# my_board.net
KiCad netlist of a schematic drawn in EAGLE
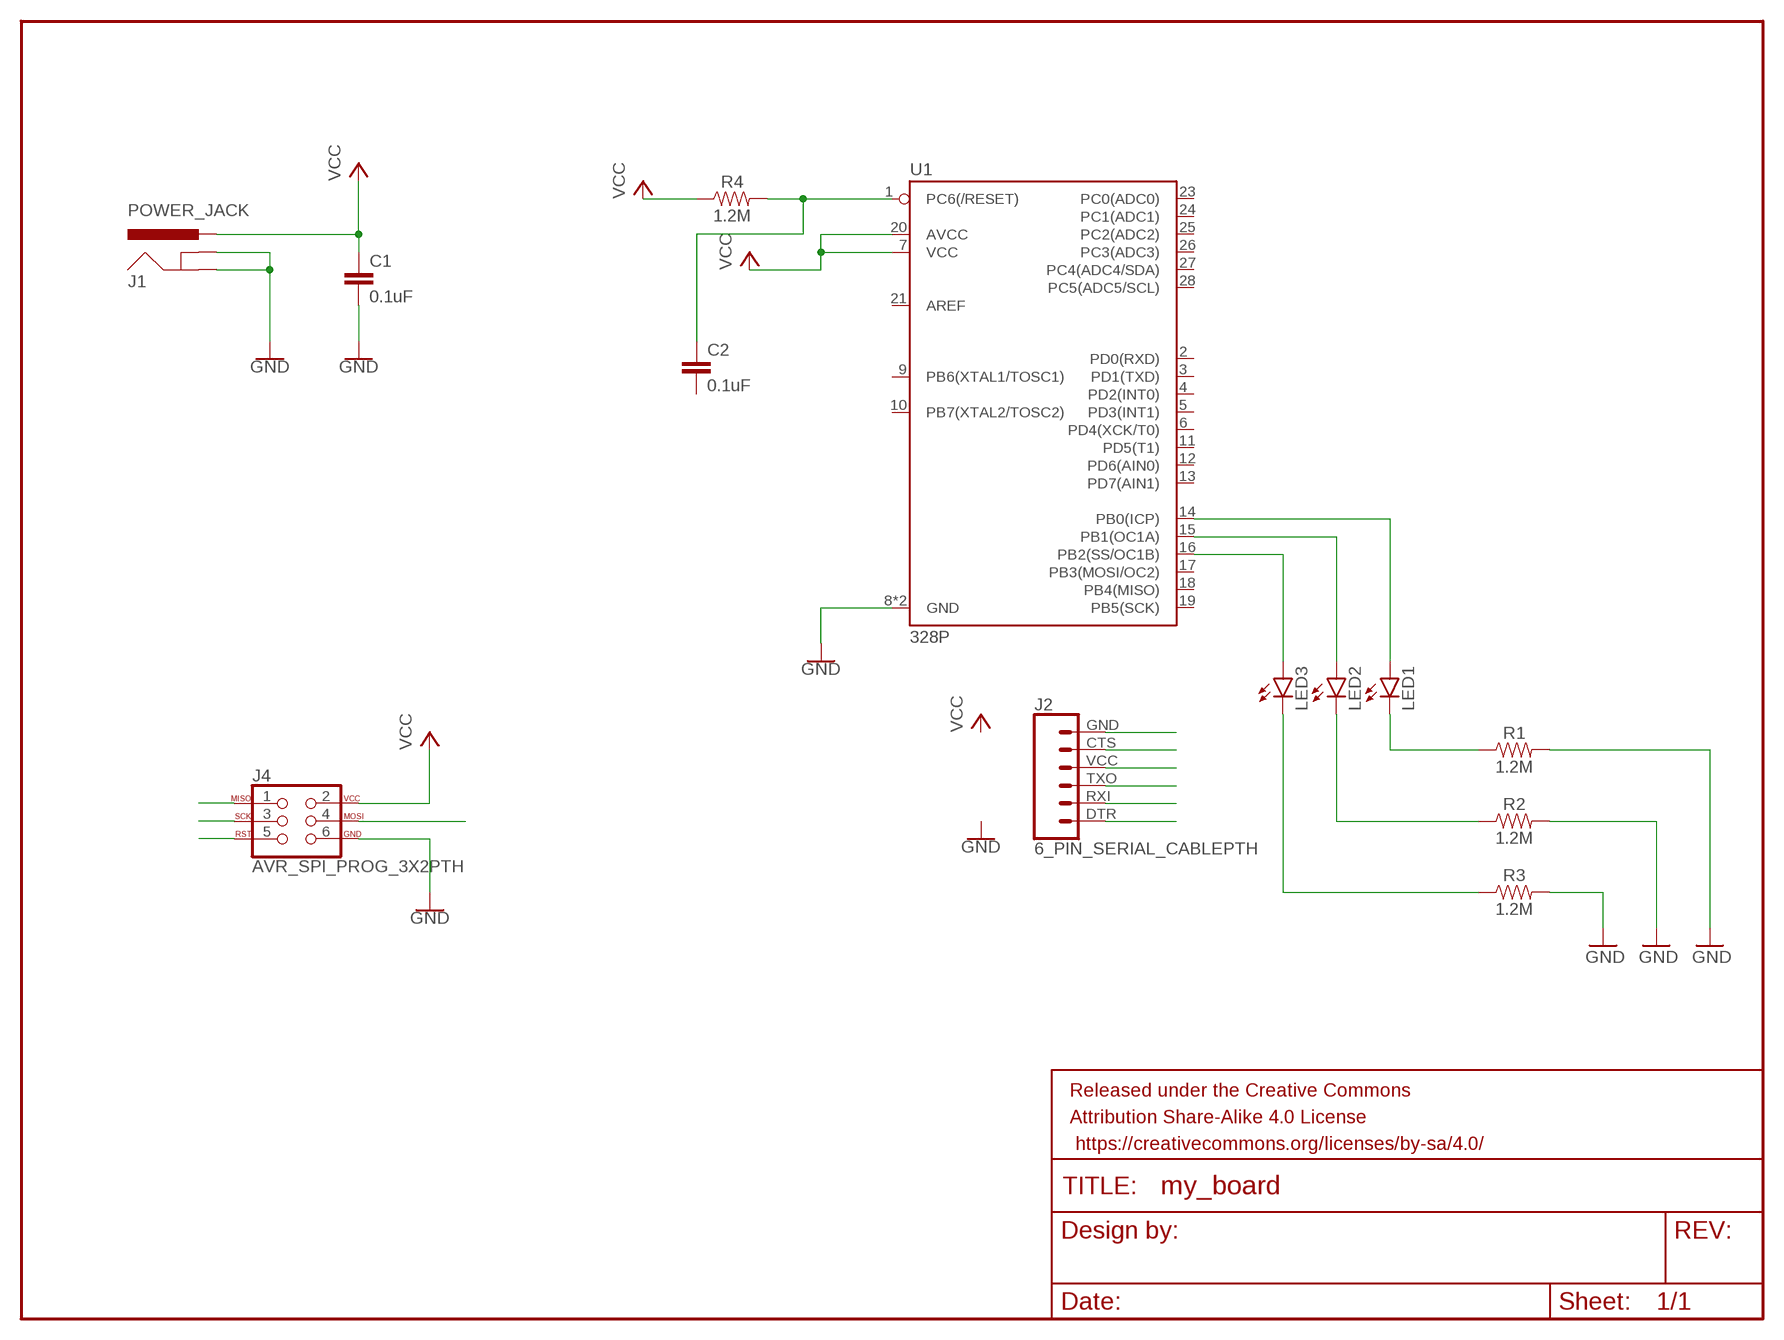
[diagram p0: schematic, sheet 1]

(export (version "E")
  (design (tool "Eeschema 10.0.6"))
  (components
    (comp (ref "C1")
      (value "0.1uF")
      (footprint "eagle-import:CAP-PTH-SMALL-KIT")
      (libsource (lib "eagle-import") (part "0.1UF-KIT-EZ-50V-20%"))
    )
    (comp (ref "C2")
      (value "0.1uF")
      (footprint "eagle-import:CAP-PTH-SMALL-KIT")
      (libsource (lib "eagle-import") (part "0.1UF-KIT-EZ-50V-20%"))
    )
    (comp (ref "FRAME1")
      (value "FRAME-LETTER")
      (footprint "eagle-import:CREATIVE_COMMONS")
      (libsource (lib "eagle-import") (part "FRAME-LETTER"))
    )
    (comp (ref "J1")
      (value "POWER_JACK")
      (footprint "eagle-import:POWER_JACK_PTH")
      (libsource (lib "eagle-import") (part "POWER_JACK"))
    )
    (comp (ref "J2")
      (value "6_PIN_SERIAL_CABLEPTH")
      (footprint "eagle-import:FTDI_BASIC")
      (libsource (lib "eagle-import") (part "6_PIN_SERIAL_CABLEPTH"))
    )
    (comp (ref "J4")
      (value "AVR_SPI_PROG_3X2PTH")
      (footprint "eagle-import:2X3")
      (libsource (lib "eagle-import") (part "AVR_SPI_PROG_3X2PTH"))
    )
    (comp (ref "LED1")
      (value "LED5MM")
      (footprint "eagle-import:LED5MM")
      (libsource (lib "eagle-import") (part "LED5MM"))
    )
    (comp (ref "LED2")
      (value "LED5MM")
      (footprint "eagle-import:LED5MM")
      (libsource (lib "eagle-import") (part "LED5MM"))
    )
    (comp (ref "LED3")
      (value "LED5MM")
      (footprint "eagle-import:LED5MM")
      (libsource (lib "eagle-import") (part "LED5MM"))
    )
    (comp (ref "R1")
      (value "1.2M")
      (footprint "eagle-import:0603")
      (libsource (lib "eagle-import") (part "1.2MOHM-0603-1/10W-1%"))
    )
    (comp (ref "R2")
      (value "1.2M")
      (footprint "eagle-import:0603")
      (libsource (lib "eagle-import") (part "1.2MOHM-0603-1/10W-1%"))
    )
    (comp (ref "R3")
      (value "1.2M")
      (footprint "eagle-import:0603")
      (libsource (lib "eagle-import") (part "1.2MOHM-0603-1/10W-1%"))
    )
    (comp (ref "R4")
      (value "1.2M")
      (footprint "eagle-import:0603")
      (libsource (lib "eagle-import") (part "1.2MOHM-0603-1/10W-1%"))
    )
    (comp (ref "U1")
      (value "328P")
      (footprint "eagle-import:DIP28")
      (libsource (lib "eagle-import") (part "ATMEGA328P_PDIP"))
    )
  )
  (nets
    (net (code "1") (name "GND") (class "Default")
      (node (ref "C1") (pin "2") (pinfunction "2_2") (pintype "passive"))
      (node (ref "J1") (pin "GND") (pinfunction "GND_GND") (pintype "bidirectional"))
      (node (ref "J1") (pin "GNDBREAK") (pinfunction "GNDBREAK_GNDBREAK") (pintype "bidirectional"))
      (node (ref "J4") (pin "6") (pinfunction "6_6") (pintype "passive"))
      (node (ref "R1") (pin "2") (pinfunction "2_2") (pintype "passive"))
      (node (ref "R2") (pin "2") (pinfunction "2_2") (pintype "passive"))
      (node (ref "R3") (pin "2") (pinfunction "2_2") (pintype "passive"))
      (node (ref "U1") (pin "22") (pinfunction "GND_22") (pintype "bidirectional"))
      (node (ref "U1") (pin "8") (pinfunction "GND_8") (pintype "bidirectional"))
    )
    (net (code "2") (name "Net-(LED1-C)") (class "Default")
      (node (ref "LED1") (pin "K") (pinfunction "C_K") (pintype "passive"))
      (node (ref "R1") (pin "1") (pinfunction "1_1") (pintype "passive"))
    )
    (net (code "3") (name "Net-(LED2-C)") (class "Default")
      (node (ref "LED2") (pin "K") (pinfunction "C_K") (pintype "passive"))
      (node (ref "R2") (pin "1") (pinfunction "1_1") (pintype "passive"))
    )
    (net (code "4") (name "Net-(LED3-C)") (class "Default")
      (node (ref "LED3") (pin "K") (pinfunction "C_K") (pintype "passive"))
      (node (ref "R3") (pin "1") (pinfunction "1_1") (pintype "passive"))
    )
    (net (code "5") (name "Net-(U1-PB0(ICP))") (class "Default")
      (node (ref "LED1") (pin "A") (pinfunction "A_A") (pintype "passive"))
      (node (ref "U1") (pin "14") (pinfunction "PB0(ICP)_14") (pintype "bidirectional"))
    )
    (net (code "6") (name "Net-(U1-PB1(OC1A))") (class "Default")
      (node (ref "LED2") (pin "A") (pinfunction "A_A") (pintype "passive"))
      (node (ref "U1") (pin "15") (pinfunction "PB1(OC1A)_15") (pintype "bidirectional"))
    )
    (net (code "7") (name "Net-(U1-PB2(SS{slash}OC1B))") (class "Default")
      (node (ref "LED3") (pin "A") (pinfunction "A_A") (pintype "passive"))
      (node (ref "U1") (pin "16") (pinfunction "PB2(SS/OC1B)_16") (pintype "bidirectional"))
    )
    (net (code "8") (name "Net-(U1-PC6({slash}RESET))") (class "Default")
      (node (ref "C2") (pin "1") (pinfunction "1_1") (pintype "passive"))
      (node (ref "R4") (pin "2") (pinfunction "2_2") (pintype "passive"))
      (node (ref "U1") (pin "1") (pinfunction "PC6(/RESET)_1") (pintype "bidirectional"))
    )
    (net (code "9") (name "VCC") (class "Default")
      (node (ref "C1") (pin "1") (pinfunction "1_1") (pintype "passive"))
      (node (ref "J1") (pin "PWR") (pinfunction "PWR_PWR") (pintype "bidirectional"))
      (node (ref "J4") (pin "2") (pinfunction "2_2") (pintype "passive"))
      (node (ref "R4") (pin "1") (pinfunction "1_1") (pintype "passive"))
      (node (ref "U1") (pin "20") (pinfunction "AVCC_20") (pintype "bidirectional"))
      (node (ref "U1") (pin "7") (pinfunction "VCC_7") (pintype "bidirectional"))
    )
    (net (code "10") (name "unconnected-(C2-Pad2)") (class "Default")
      (node (ref "C2") (pin "2") (pinfunction "2_2") (pintype "passive"))
    )
    (net (code "11") (name "unconnected-(J2-1-PadDTR)") (class "Default")
      (node (ref "J2") (pin "DTR") (pinfunction "1_DTR") (pintype "passive"))
    )
    (net (code "12") (name "unconnected-(J2-2-PadRXI)") (class "Default")
      (node (ref "J2") (pin "RXI") (pinfunction "2_RXI") (pintype "passive"))
    )
    (net (code "13") (name "unconnected-(J2-3-PadTXO)") (class "Default")
      (node (ref "J2") (pin "TXO") (pinfunction "3_TXO") (pintype "passive"))
    )
    (net (code "14") (name "unconnected-(J2-4-PadVCC)") (class "Default")
      (node (ref "J2") (pin "VCC") (pinfunction "4_VCC") (pintype "passive"))
    )
    (net (code "15") (name "unconnected-(J2-5-PadCTS)") (class "Default")
      (node (ref "J2") (pin "CTS") (pinfunction "5_CTS") (pintype "passive"))
    )
    (net (code "16") (name "unconnected-(J2-6-PadGND)") (class "Default")
      (node (ref "J2") (pin "GND") (pinfunction "6_GND") (pintype "passive"))
    )
    (net (code "17") (name "unconnected-(J4-Pad1)") (class "Default")
      (node (ref "J4") (pin "1") (pinfunction "1_1") (pintype "passive"))
    )
    (net (code "18") (name "unconnected-(J4-Pad3)") (class "Default")
      (node (ref "J4") (pin "3") (pinfunction "3_3") (pintype "passive"))
    )
    (net (code "19") (name "unconnected-(J4-Pad4)") (class "Default")
      (node (ref "J4") (pin "4") (pinfunction "4_4") (pintype "passive"))
    )
    (net (code "20") (name "unconnected-(J4-Pad5)") (class "Default")
      (node (ref "J4") (pin "5") (pinfunction "5_5") (pintype "passive"))
    )
    (net (code "21") (name "unconnected-(U1-AREF-Pad21)") (class "Default")
      (node (ref "U1") (pin "21") (pinfunction "AREF_21") (pintype "bidirectional"))
    )
    (net (code "22") (name "unconnected-(U1-PB3(MOSI{slash}OC2)-Pad17)") (class "Default")
      (node (ref "U1") (pin "17") (pinfunction "PB3(MOSI/OC2)_17") (pintype "bidirectional"))
    )
    (net (code "23") (name "unconnected-(U1-PB4(MISO)-Pad18)") (class "Default")
      (node (ref "U1") (pin "18") (pinfunction "PB4(MISO)_18") (pintype "bidirectional"))
    )
    (net (code "24") (name "unconnected-(U1-PB5(SCK)-Pad19)") (class "Default")
      (node (ref "U1") (pin "19") (pinfunction "PB5(SCK)_19") (pintype "bidirectional"))
    )
    (net (code "25") (name "unconnected-(U1-PB6(XTAL1{slash}TOSC1)-Pad9)") (class "Default")
      (node (ref "U1") (pin "9") (pinfunction "PB6(XTAL1/TOSC1)_9") (pintype "bidirectional"))
    )
    (net (code "26") (name "unconnected-(U1-PB7(XTAL2{slash}TOSC2)-Pad10)") (class "Default")
      (node (ref "U1") (pin "10") (pinfunction "PB7(XTAL2/TOSC2)_10") (pintype "bidirectional"))
    )
    (net (code "27") (name "unconnected-(U1-PC0(ADC0)-Pad23)") (class "Default")
      (node (ref "U1") (pin "23") (pinfunction "PC0(ADC0)_23") (pintype "bidirectional"))
    )
    (net (code "28") (name "unconnected-(U1-PC1(ADC1)-Pad24)") (class "Default")
      (node (ref "U1") (pin "24") (pinfunction "PC1(ADC1)_24") (pintype "bidirectional"))
    )
    (net (code "29") (name "unconnected-(U1-PC2(ADC2)-Pad25)") (class "Default")
      (node (ref "U1") (pin "25") (pinfunction "PC2(ADC2)_25") (pintype "bidirectional"))
    )
    (net (code "30") (name "unconnected-(U1-PC3(ADC3)-Pad26)") (class "Default")
      (node (ref "U1") (pin "26") (pinfunction "PC3(ADC3)_26") (pintype "bidirectional"))
    )
    (net (code "31") (name "unconnected-(U1-PC4(ADC4{slash}SDA)-Pad27)") (class "Default")
      (node (ref "U1") (pin "27") (pinfunction "PC4(ADC4/SDA)_27") (pintype "bidirectional"))
    )
    (net (code "32") (name "unconnected-(U1-PC5(ADC5{slash}SCL)-Pad28)") (class "Default")
      (node (ref "U1") (pin "28") (pinfunction "PC5(ADC5/SCL)_28") (pintype "bidirectional"))
    )
    (net (code "33") (name "unconnected-(U1-PD0(RXD)-Pad2)") (class "Default")
      (node (ref "U1") (pin "2") (pinfunction "PD0(RXD)_2") (pintype "bidirectional"))
    )
    (net (code "34") (name "unconnected-(U1-PD1(TXD)-Pad3)") (class "Default")
      (node (ref "U1") (pin "3") (pinfunction "PD1(TXD)_3") (pintype "bidirectional"))
    )
    (net (code "35") (name "unconnected-(U1-PD2(INT0)-Pad4)") (class "Default")
      (node (ref "U1") (pin "4") (pinfunction "PD2(INT0)_4") (pintype "bidirectional"))
    )
    (net (code "36") (name "unconnected-(U1-PD3(INT1)-Pad5)") (class "Default")
      (node (ref "U1") (pin "5") (pinfunction "PD3(INT1)_5") (pintype "bidirectional"))
    )
    (net (code "37") (name "unconnected-(U1-PD4(XCK{slash}T0)-Pad6)") (class "Default")
      (node (ref "U1") (pin "6") (pinfunction "PD4(XCK/T0)_6") (pintype "bidirectional"))
    )
    (net (code "38") (name "unconnected-(U1-PD5(T1)-Pad11)") (class "Default")
      (node (ref "U1") (pin "11") (pinfunction "PD5(T1)_11") (pintype "bidirectional"))
    )
    (net (code "39") (name "unconnected-(U1-PD6(AIN0)-Pad12)") (class "Default")
      (node (ref "U1") (pin "12") (pinfunction "PD6(AIN0)_12") (pintype "bidirectional"))
    )
    (net (code "40") (name "unconnected-(U1-PD7(AIN1)-Pad13)") (class "Default")
      (node (ref "U1") (pin "13") (pinfunction "PD7(AIN1)_13") (pintype "bidirectional"))
    )
  )
)
